# V5_8-18-09-27.net
KiCad netlist of a schematic drawn in EAGLE
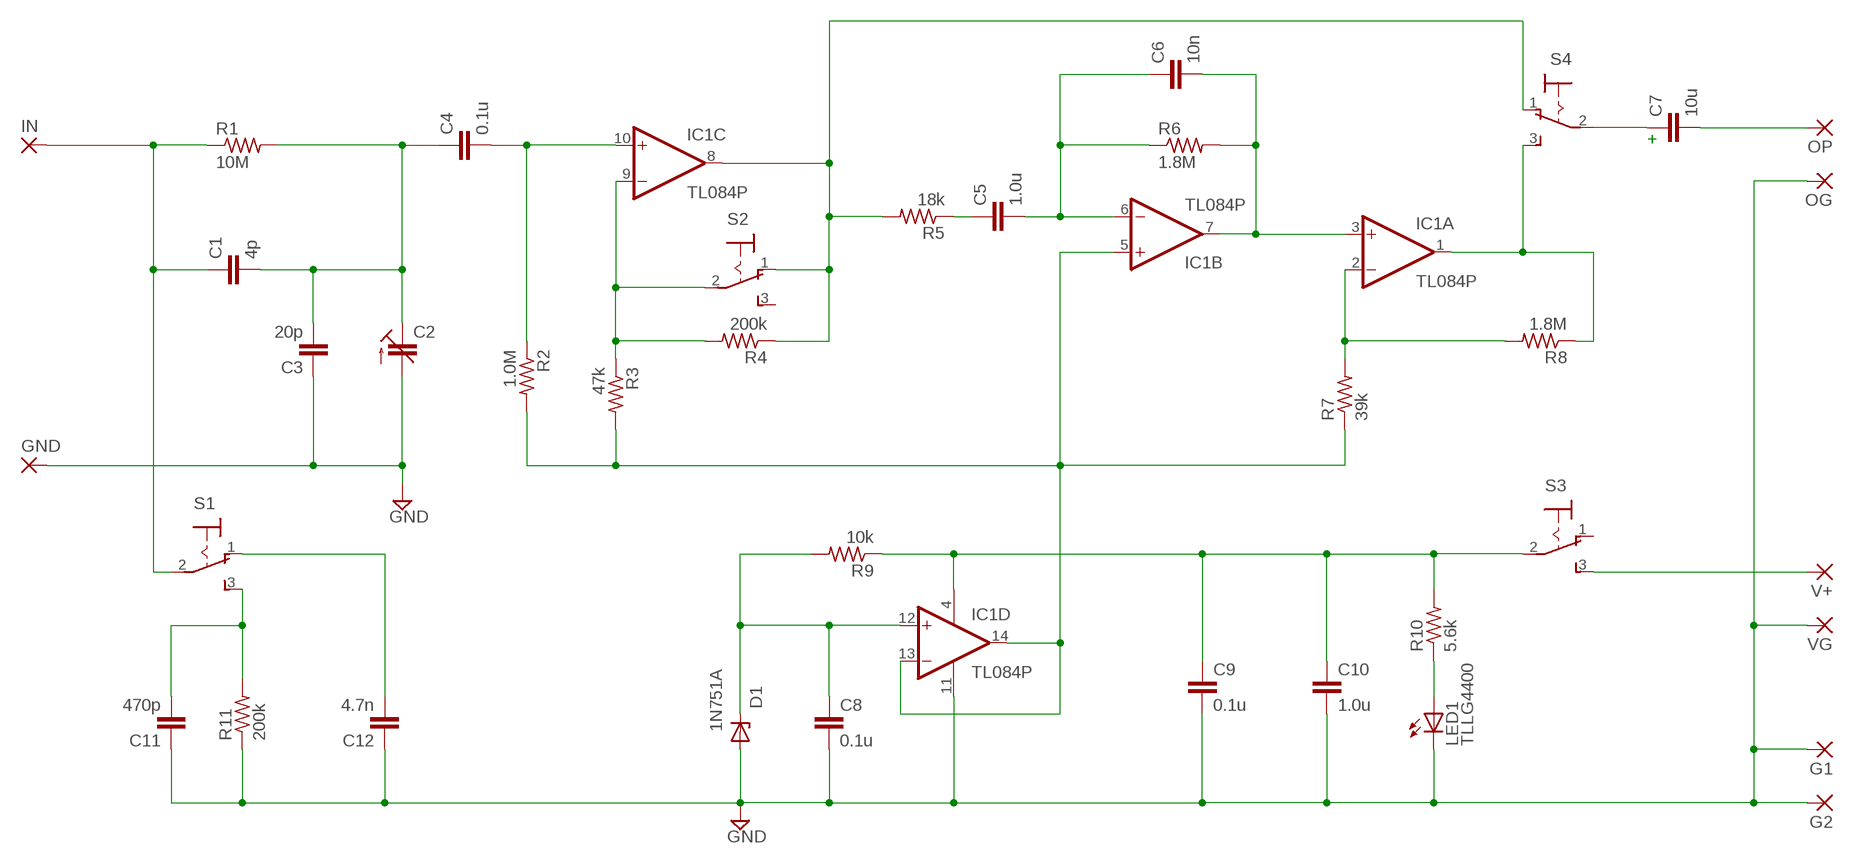
[diagram p0: schematic, sheet 1]

(export (version "E")
  (design (tool "Eeschema 10.0.6"))
  (components
    (comp (ref "C1")
      (value "4p")
      (footprint "eagle-import:C050-024X044")
      (libsource (lib "eagle-import") (part "C-EU050-024X044"))
    )
    (comp (ref "C2")
      (value "C-TRIMMGKG20015")
      (footprint "eagle-import:GKG20015")
      (libsource (lib "eagle-import") (part "C-TRIMMGKG20015"))
    )
    (comp (ref "C3")
      (value "20p")
      (footprint "eagle-import:C050-024X044")
      (libsource (lib "eagle-import") (part "C-EU050-024X044"))
    )
    (comp (ref "C4")
      (value "0.1u")
      (footprint "eagle-import:C050-024X044")
      (libsource (lib "eagle-import") (part "C-EU050-024X044"))
    )
    (comp (ref "C5")
      (value "1.0u")
      (footprint "eagle-import:C050-024X044")
      (libsource (lib "eagle-import") (part "C-EU050-024X044"))
    )
    (comp (ref "C6")
      (value "10n")
      (footprint "eagle-import:C050-024X044")
      (libsource (lib "eagle-import") (part "C-EU050-024X044"))
    )
    (comp (ref "C7")
      (value "10u")
      (footprint "eagle-import:C050-024X044")
      (libsource (lib "eagle-import") (part "C-EU050-024X044"))
    )
    (comp (ref "C8")
      (value "0.1u")
      (footprint "eagle-import:C050-024X044")
      (libsource (lib "eagle-import") (part "C-EU050-024X044"))
    )
    (comp (ref "C9")
      (value "0.1u")
      (footprint "eagle-import:C050-024X044")
      (libsource (lib "eagle-import") (part "C-EU050-024X044"))
    )
    (comp (ref "C10")
      (value "1.0u")
      (footprint "eagle-import:C050-024X044")
      (libsource (lib "eagle-import") (part "C-EU050-024X044"))
    )
    (comp (ref "C11")
      (value "470p")
      (footprint "eagle-import:C050-024X044")
      (libsource (lib "eagle-import") (part "C-EU050-024X044"))
    )
    (comp (ref "C12")
      (value "4.7n")
      (footprint "eagle-import:C050-024X044")
      (libsource (lib "eagle-import") (part "C-EU050-024X044"))
    )
    (comp (ref "D1")
      (value "ZENER-DIODEDO35Z10")
      (footprint "eagle-import:DO35Z10")
      (libsource (lib "eagle-import") (part "ZENER-DIODEDO35Z10"))
    )
    (comp (ref "G1")
      (value "2,54/1,1")
      (footprint "eagle-import:2,54_1,1")
      (libsource (lib "eagle-import") (part "2,54/1,1"))
    )
    (comp (ref "G2")
      (value "2,54/1,1")
      (footprint "eagle-import:2,54_1,1")
      (libsource (lib "eagle-import") (part "2,54/1,1"))
    )
    (comp (ref "GND")
      (value "2,54/1,1")
      (footprint "eagle-import:2,54_1,1")
      (libsource (lib "eagle-import") (part "2,54/1,1"))
    )
    (comp (ref "IC1")
      (value "TL084P")
      (footprint "eagle-import:DIL14")
      (libsource (lib "eagle-import") (part "TL084P"))
    )
    (comp (ref "IN")
      (value "2,54/1,1")
      (footprint "eagle-import:2,54_1,1")
      (libsource (lib "eagle-import") (part "2,54/1,1"))
    )
    (comp (ref "LED1")
      (value "TLLG4400")
      (footprint "eagle-import:LED3MM")
      (fields (field (name "MF") "VISHAY SEMICONDUCTOR"))
      (libsource (lib "eagle-import") (part "TLLG4400"))
    )
    (comp (ref "OG")
      (value "2,54/1,1")
      (footprint "eagle-import:2,54_1,1")
      (libsource (lib "eagle-import") (part "2,54/1,1"))
    )
    (comp (ref "OP")
      (value "2,54/1,1")
      (footprint "eagle-import:2,54_1,1")
      (libsource (lib "eagle-import") (part "2,54/1,1"))
    )
    (comp (ref "R1")
      (value "10M")
      (footprint "eagle-import:0207_10")
      (libsource (lib "eagle-import") (part "R-US_0207/10"))
    )
    (comp (ref "R2")
      (value "1.0M")
      (footprint "eagle-import:0207_10")
      (libsource (lib "eagle-import") (part "R-US_0207/10"))
    )
    (comp (ref "R3")
      (value "47k")
      (footprint "eagle-import:0207_10")
      (libsource (lib "eagle-import") (part "R-US_0207/10"))
    )
    (comp (ref "R4")
      (value "200k")
      (footprint "eagle-import:0207_10")
      (libsource (lib "eagle-import") (part "R-US_0207/10"))
    )
    (comp (ref "R5")
      (value "18k")
      (footprint "eagle-import:0207_10")
      (libsource (lib "eagle-import") (part "R-US_0207/10"))
    )
    (comp (ref "R6")
      (value "1.8M")
      (footprint "eagle-import:0207_10")
      (libsource (lib "eagle-import") (part "R-US_0207/10"))
    )
    (comp (ref "R7")
      (value "39k")
      (footprint "eagle-import:0207_10")
      (libsource (lib "eagle-import") (part "R-US_0207/10"))
    )
    (comp (ref "R8")
      (value "1.8M")
      (footprint "eagle-import:0207_10")
      (libsource (lib "eagle-import") (part "R-US_0207/10"))
    )
    (comp (ref "R9")
      (value "10k")
      (footprint "eagle-import:0207_10")
      (libsource (lib "eagle-import") (part "R-US_0207/10"))
    )
    (comp (ref "R10")
      (value "5.6k")
      (footprint "eagle-import:0207_10")
      (libsource (lib "eagle-import") (part "R-US_0207/10"))
    )
    (comp (ref "R11")
      (value "200k")
      (footprint "eagle-import:0207_10")
      (libsource (lib "eagle-import") (part "R-US_0207/10"))
    )
    (comp (ref "S1")
      (value "320-916")
      (footprint "eagle-import:320-916")
      (libsource (lib "eagle-import") (part "320-916"))
    )
    (comp (ref "S2")
      (value "320-916")
      (footprint "eagle-import:320-916")
      (libsource (lib "eagle-import") (part "320-916"))
    )
    (comp (ref "S3")
      (value "320-916")
      (footprint "eagle-import:320-916")
      (libsource (lib "eagle-import") (part "320-916"))
    )
    (comp (ref "S4")
      (value "320-916")
      (footprint "eagle-import:320-916")
      (libsource (lib "eagle-import") (part "320-916"))
    )
    (comp (ref "V+")
      (value "2,54/1,1")
      (footprint "eagle-import:2,54_1,1")
      (libsource (lib "eagle-import") (part "2,54/1,1"))
    )
    (comp (ref "VG")
      (value "2,54/1,1")
      (footprint "eagle-import:2,54_1,1")
      (libsource (lib "eagle-import") (part "2,54/1,1"))
    )
  )
  (nets
    (net (code "1") (name "GND") (class "Default")
      (node (ref "C10") (pin "2") (pinfunction "2_2") (pintype "passive"))
      (node (ref "C11") (pin "1") (pinfunction "1_1") (pintype "passive"))
      (node (ref "C12") (pin "1") (pinfunction "1_1") (pintype "passive"))
      (node (ref "C2") (pin "1") (pinfunction "A_1") (pintype "passive"))
      (node (ref "C3") (pin "1") (pinfunction "1_1") (pintype "passive"))
      (node (ref "C8") (pin "2") (pinfunction "2_2") (pintype "passive"))
      (node (ref "C9") (pin "2") (pinfunction "2_2") (pintype "passive"))
      (node (ref "D1") (pin "A") (pinfunction "A_A") (pintype "passive"))
      (node (ref "G1") (pin "1") (pinfunction "P_1") (pintype "passive"))
      (node (ref "G2") (pin "1") (pinfunction "P_1") (pintype "passive"))
      (node (ref "GND") (pin "1") (pinfunction "P_1") (pintype "passive"))
      (node (ref "IC1") (pin "11") (pinfunction "V-_11") (pintype "power_in"))
      (node (ref "LED1") (pin "K") (pinfunction "C_K") (pintype "passive"))
      (node (ref "OG") (pin "1") (pinfunction "P_1") (pintype "passive"))
      (node (ref "R11") (pin "1") (pinfunction "1_1") (pintype "passive"))
      (node (ref "VG") (pin "1") (pinfunction "P_1") (pintype "passive"))
    )
    (net (code "2") (name "Net-(C2-E)") (class "Default")
      (node (ref "C1") (pin "2") (pinfunction "2_2") (pintype "passive"))
      (node (ref "C2") (pin "2") (pinfunction "E_2") (pintype "passive"))
      (node (ref "C3") (pin "2") (pinfunction "2_2") (pintype "passive"))
      (node (ref "C4") (pin "1") (pinfunction "1_1") (pintype "passive"))
      (node (ref "R1") (pin "2") (pinfunction "2_2") (pintype "passive"))
    )
    (net (code "3") (name "Net-(C5-Pad1)") (class "Default")
      (node (ref "C5") (pin "1") (pinfunction "1_1") (pintype "passive"))
      (node (ref "R5") (pin "1") (pinfunction "1_1") (pintype "passive"))
    )
    (net (code "4") (name "Net-(IC1A-+IN)") (class "Default")
      (node (ref "C6") (pin "2") (pinfunction "2_2") (pintype "passive"))
      (node (ref "IC1") (pin "3") (pinfunction "+IN_3") (pintype "input"))
      (node (ref "IC1") (pin "7") (pinfunction "OUT_7") (pintype "output"))
      (node (ref "R6") (pin "2") (pinfunction "2_2") (pintype "passive"))
    )
    (net (code "5") (name "Net-(IC1A--IN)") (class "Default")
      (node (ref "IC1") (pin "2") (pinfunction "-IN_2") (pintype "input"))
      (node (ref "R7") (pin "2") (pinfunction "2_2") (pintype "passive"))
      (node (ref "R8") (pin "2") (pinfunction "2_2") (pintype "passive"))
    )
    (net (code "6") (name "Net-(IC1A-OUT)") (class "Default")
      (node (ref "IC1") (pin "1") (pinfunction "OUT_1") (pintype "output"))
      (node (ref "R8") (pin "1") (pinfunction "1_1") (pintype "passive"))
      (node (ref "S4") (pin "3") (pinfunction "S_3") (pintype "passive"))
    )
    (net (code "7") (name "Net-(IC1B-+IN)") (class "Default")
      (node (ref "IC1") (pin "13") (pinfunction "-IN_13") (pintype "input"))
      (node (ref "IC1") (pin "14") (pinfunction "OUT_14") (pintype "output"))
      (node (ref "IC1") (pin "5") (pinfunction "+IN_5") (pintype "input"))
      (node (ref "R2") (pin "2") (pinfunction "2_2") (pintype "passive"))
      (node (ref "R3") (pin "2") (pinfunction "2_2") (pintype "passive"))
      (node (ref "R7") (pin "1") (pinfunction "1_1") (pintype "passive"))
    )
    (net (code "8") (name "Net-(IC1B--IN)") (class "Default")
      (node (ref "C5") (pin "2") (pinfunction "2_2") (pintype "passive"))
      (node (ref "C6") (pin "1") (pinfunction "1_1") (pintype "passive"))
      (node (ref "IC1") (pin "6") (pinfunction "-IN_6") (pintype "input"))
      (node (ref "R6") (pin "1") (pinfunction "1_1") (pintype "passive"))
    )
    (net (code "9") (name "Net-(IC1C-+IN)") (class "Default")
      (node (ref "C4") (pin "2") (pinfunction "2_2") (pintype "passive"))
      (node (ref "IC1") (pin "10") (pinfunction "+IN_10") (pintype "input"))
      (node (ref "R2") (pin "1") (pinfunction "1_1") (pintype "passive"))
    )
    (net (code "10") (name "Net-(IC1C--IN)") (class "Default")
      (node (ref "IC1") (pin "9") (pinfunction "-IN_9") (pintype "input"))
      (node (ref "R3") (pin "1") (pinfunction "1_1") (pintype "passive"))
      (node (ref "R4") (pin "2") (pinfunction "2_2") (pintype "passive"))
      (node (ref "S2") (pin "2") (pinfunction "P_2") (pintype "passive"))
    )
    (net (code "11") (name "Net-(IC1C-OUT)") (class "Default")
      (node (ref "IC1") (pin "8") (pinfunction "OUT_8") (pintype "output"))
      (node (ref "R4") (pin "1") (pinfunction "1_1") (pintype "passive"))
      (node (ref "R5") (pin "2") (pinfunction "2_2") (pintype "passive"))
      (node (ref "S2") (pin "1") (pinfunction "O_1") (pintype "passive"))
      (node (ref "S4") (pin "1") (pinfunction "O_1") (pintype "passive"))
    )
    (net (code "12") (name "Net-(IC1D-+IN)") (class "Default")
      (node (ref "C8") (pin "1") (pinfunction "1_1") (pintype "passive"))
      (node (ref "D1") (pin "C") (pinfunction "C_C") (pintype "passive"))
      (node (ref "IC1") (pin "12") (pinfunction "+IN_12") (pintype "input"))
      (node (ref "R9") (pin "2") (pinfunction "2_2") (pintype "passive"))
    )
    (net (code "13") (name "Net-(IC1E-V+)") (class "Default")
      (node (ref "C10") (pin "1") (pinfunction "1_1") (pintype "passive"))
      (node (ref "C9") (pin "1") (pinfunction "1_1") (pintype "passive"))
      (node (ref "IC1") (pin "4") (pinfunction "V+_4") (pintype "power_in"))
      (node (ref "R10") (pin "2") (pinfunction "2_2") (pintype "passive"))
      (node (ref "R9") (pin "1") (pinfunction "1_1") (pintype "passive"))
      (node (ref "S3") (pin "2") (pinfunction "P_2") (pintype "passive"))
    )
    (net (code "14") (name "Net-(IN-P)") (class "Default")
      (node (ref "C1") (pin "1") (pinfunction "1_1") (pintype "passive"))
      (node (ref "IN") (pin "1") (pinfunction "P_1") (pintype "passive"))
      (node (ref "R1") (pin "1") (pinfunction "1_1") (pintype "passive"))
      (node (ref "S1") (pin "2") (pinfunction "P_2") (pintype "passive"))
    )
    (net (code "15") (name "Net-(LED1-PadA)") (class "Default")
      (node (ref "LED1") (pin "A") (pinfunction "A_A") (pintype "passive"))
      (node (ref "R10") (pin "1") (pinfunction "1_1") (pintype "passive"))
    )
    (net (code "16") (name "Net-(OP-P)") (class "Default")
      (node (ref "C7") (pin "2") (pinfunction "2_2") (pintype "passive"))
      (node (ref "OP") (pin "1") (pinfunction "P_1") (pintype "passive"))
    )
    (net (code "17") (name "Net-(S1-O)") (class "Default")
      (node (ref "C12") (pin "2") (pinfunction "2_2") (pintype "passive"))
      (node (ref "S1") (pin "1") (pinfunction "O_1") (pintype "passive"))
    )
    (net (code "18") (name "Net-(S1-S)") (class "Default")
      (node (ref "C11") (pin "2") (pinfunction "2_2") (pintype "passive"))
      (node (ref "R11") (pin "2") (pinfunction "2_2") (pintype "passive"))
      (node (ref "S1") (pin "3") (pinfunction "S_3") (pintype "passive"))
    )
    (net (code "19") (name "Net-(S3-S)") (class "Default")
      (node (ref "S3") (pin "3") (pinfunction "S_3") (pintype "passive"))
      (node (ref "V+") (pin "1") (pinfunction "P_1") (pintype "passive"))
    )
    (net (code "20") (name "Net-(S4-P)") (class "Default")
      (node (ref "C7") (pin "1") (pinfunction "1_1") (pintype "passive"))
      (node (ref "S4") (pin "2") (pinfunction "P_2") (pintype "passive"))
    )
    (net (code "21") (name "unconnected-(S2-S-Pad3)") (class "Default")
      (node (ref "S2") (pin "3") (pinfunction "S_3") (pintype "passive"))
    )
    (net (code "22") (name "unconnected-(S3-O-Pad1)") (class "Default")
      (node (ref "S3") (pin "1") (pinfunction "O_1") (pintype "passive"))
    )
  )
)
